# I2C-OneWire_Probes.net
KiCad netlist of a schematic drawn in EAGLE
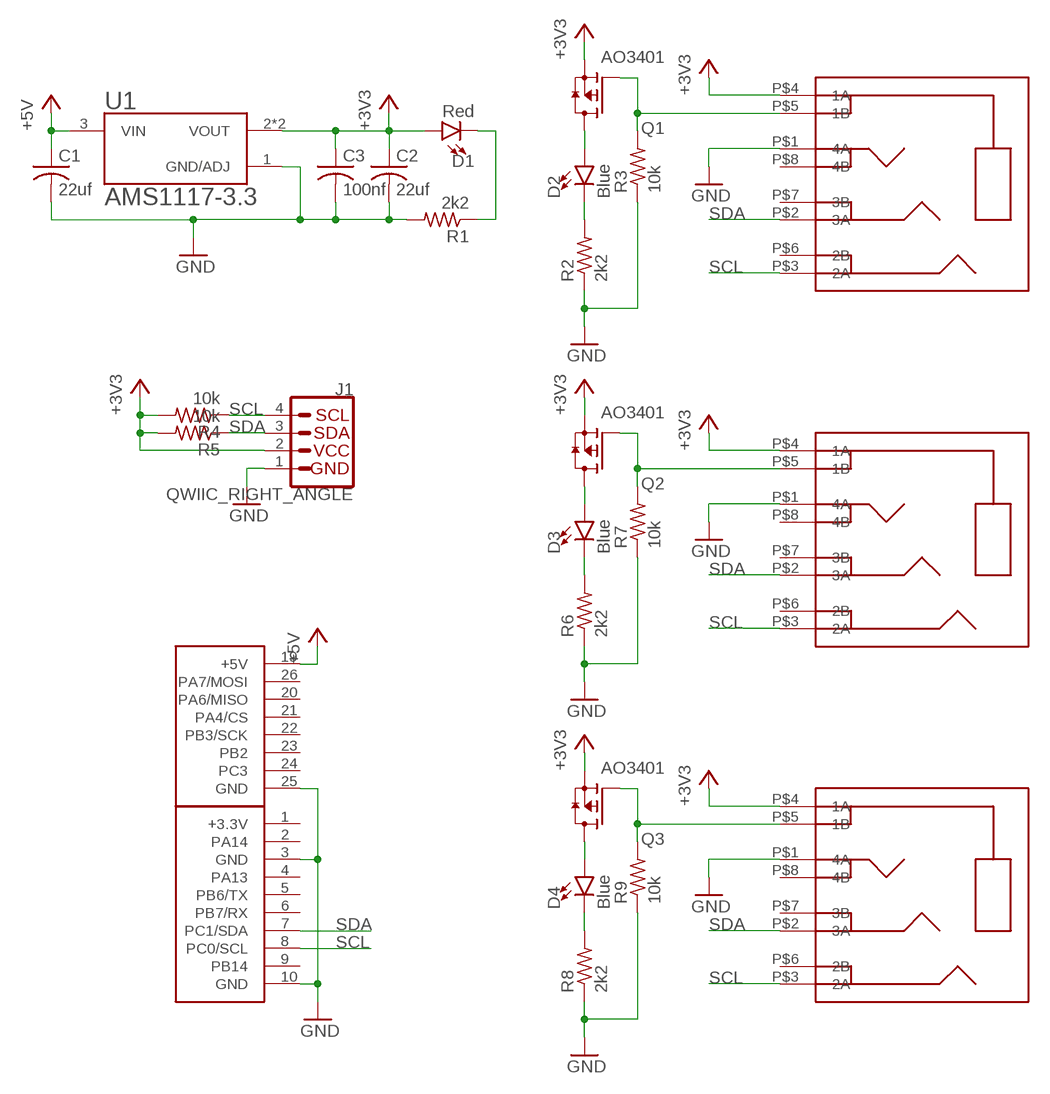
[diagram p0: schematic, sheet 1]

(export (version "E")
  (design (tool "Eeschema 10.0.6"))
  (components
    (comp (ref "C1")
      (value "22uf")
      (footprint "eagle-import:C3216")
      (libsource (lib "eagle-import") (part "C-USC3216"))
    )
    (comp (ref "C2")
      (value "22uf")
      (footprint "eagle-import:C3216")
      (libsource (lib "eagle-import") (part "C-USC3216"))
    )
    (comp (ref "C3")
      (value "100nf")
      (footprint "eagle-import:C0805")
      (libsource (lib "eagle-import") (part "C-USC0805"))
    )
    (comp (ref "D1")
      (value "Red")
      (footprint "eagle-import:LED-1206")
      (libsource (lib "eagle-import") (part "LED-RED1206"))
    )
    (comp (ref "D2")
      (value "Blue")
      (footprint "eagle-import:LED-1206")
      (libsource (lib "eagle-import") (part "LED-BLUE1206"))
    )
    (comp (ref "D3")
      (value "Blue")
      (footprint "eagle-import:LED-1206")
      (libsource (lib "eagle-import") (part "LED-BLUE1206"))
    )
    (comp (ref "D4")
      (value "Blue")
      (footprint "eagle-import:LED-1206")
      (libsource (lib "eagle-import") (part "LED-BLUE1206"))
    )
    (comp (ref "J1")
      (value "QWIIC_RIGHT_ANGLE")
      (footprint "eagle-import:JST04_1MM_RA")
      (libsource (lib "eagle-import") (part "QWIIC_CONNECTORJS-1MM"))
    )
    (comp (ref "Q1")
      (value "AO3401")
      (footprint "eagle-import:AO3401")
      (fields (field (name "MANUFACTURER") "Diodes Inc."))
      (libsource (lib "eagle-import") (part "AO3401"))
    )
    (comp (ref "Q2")
      (value "AO3401")
      (footprint "eagle-import:AO3401")
      (fields (field (name "MANUFACTURER") "Diodes Inc."))
      (libsource (lib "eagle-import") (part "AO3401"))
    )
    (comp (ref "Q3")
      (value "AO3401")
      (footprint "eagle-import:AO3401")
      (fields (field (name "MANUFACTURER") "Diodes Inc."))
      (libsource (lib "eagle-import") (part "AO3401"))
    )
    (comp (ref "R1")
      (value "2k2")
      (footprint "eagle-import:R0805")
      (libsource (lib "eagle-import") (part "R-US_R0805"))
    )
    (comp (ref "R2")
      (value "2k2")
      (footprint "eagle-import:R0805")
      (libsource (lib "eagle-import") (part "R-US_R0805"))
    )
    (comp (ref "R3")
      (value "10k")
      (footprint "eagle-import:R0805")
      (libsource (lib "eagle-import") (part "R-US_R0805"))
    )
    (comp (ref "R4")
      (value "10k")
      (footprint "eagle-import:R0805")
      (libsource (lib "eagle-import") (part "R-US_R0805"))
    )
    (comp (ref "R5")
      (value "10k")
      (footprint "eagle-import:R0805")
      (libsource (lib "eagle-import") (part "R-US_R0805"))
    )
    (comp (ref "R6")
      (value "2k2")
      (footprint "eagle-import:R0805")
      (libsource (lib "eagle-import") (part "R-US_R0805"))
    )
    (comp (ref "R7")
      (value "10k")
      (footprint "eagle-import:R0805")
      (libsource (lib "eagle-import") (part "R-US_R0805"))
    )
    (comp (ref "R8")
      (value "2k2")
      (footprint "eagle-import:R0805")
      (libsource (lib "eagle-import") (part "R-US_R0805"))
    )
    (comp (ref "R9")
      (value "10k")
      (footprint "eagle-import:R0805")
      (libsource (lib "eagle-import") (part "R-US_R0805"))
    )
    (comp (ref "U$1")
      (value "BOTH-SMD")
      (footprint "eagle-import:BOTH-SMD")
      (libsource (lib "eagle-import") (part "BOTH-SMD"))
    )
    (comp (ref "U$2")
      (value "PJ-3938PJ")
      (footprint "eagle-import:PJ-3938PJ")
      (libsource (lib "eagle-import") (part "PJ-3938PJ"))
    )
    (comp (ref "U$3")
      (value "PJ-3938PJ")
      (footprint "eagle-import:PJ-3938PJ")
      (libsource (lib "eagle-import") (part "PJ-3938PJ"))
    )
    (comp (ref "U$4")
      (value "PJ-3938PJ")
      (footprint "eagle-import:PJ-3938PJ")
      (libsource (lib "eagle-import") (part "PJ-3938PJ"))
    )
    (comp (ref "U1")
      (value "AMS1117-3.3")
      (footprint "eagle-import:SOT229P700X180-4N")
      (fields (field (name "MF") "Advanced Monolithic Systems"))
      (libsource (lib "eagle-import") (part "AMS1117-3.3"))
    )
  )
  (nets
    (net (code "1") (name "+3V3") (class "Default")
      (node (ref "C2") (pin "1") (pinfunction "1_1") (pintype "passive"))
      (node (ref "C3") (pin "1") (pinfunction "1_1") (pintype "passive"))
      (node (ref "D1") (pin "A") (pinfunction "A_A") (pintype "passive"))
      (node (ref "J1") (pin "2") (pinfunction "2_2") (pintype "power_in"))
      (node (ref "Q1") (pin "2") (pinfunction "S_2") (pintype "passive"))
      (node (ref "Q2") (pin "2") (pinfunction "S_2") (pintype "passive"))
      (node (ref "Q3") (pin "2") (pinfunction "S_2") (pintype "passive"))
      (node (ref "R4") (pin "2") (pinfunction "2_2") (pintype "passive"))
      (node (ref "R5") (pin "2") (pinfunction "2_2") (pintype "passive"))
      (node (ref "U$2") (pin "P$4") (pinfunction "1A_P$4") (pintype "bidirectional"))
      (node (ref "U$3") (pin "P$4") (pinfunction "1A_P$4") (pintype "bidirectional"))
      (node (ref "U$4") (pin "P$4") (pinfunction "1A_P$4") (pintype "bidirectional"))
      (node (ref "U1") (pin "2") (pinfunction "VOUT_2") (pintype "output"))
      (node (ref "U1") (pin "4") (pinfunction "VOUT_4") (pintype "output"))
    )
    (net (code "2") (name "+5V") (class "Default")
      (node (ref "C1") (pin "1") (pinfunction "1_1") (pintype "passive"))
      (node (ref "U$1") (pin "19") (pinfunction "+5V_19") (pintype "bidirectional"))
      (node (ref "U1") (pin "3") (pinfunction "VIN_3") (pintype "input"))
    )
    (net (code "3") (name "/SCL") (class "Default")
      (node (ref "J1") (pin "4") (pinfunction "4_4") (pintype "passive"))
      (node (ref "R4") (pin "1") (pinfunction "1_1") (pintype "passive"))
      (node (ref "U$1") (pin "8") (pinfunction "PC0/SCL_8") (pintype "bidirectional"))
      (node (ref "U$2") (pin "P$3") (pinfunction "2A_P$3") (pintype "bidirectional"))
      (node (ref "U$3") (pin "P$3") (pinfunction "2A_P$3") (pintype "bidirectional"))
      (node (ref "U$4") (pin "P$3") (pinfunction "2A_P$3") (pintype "bidirectional"))
    )
    (net (code "4") (name "/SDA") (class "Default")
      (node (ref "J1") (pin "3") (pinfunction "3_3") (pintype "passive"))
      (node (ref "R5") (pin "1") (pinfunction "1_1") (pintype "passive"))
      (node (ref "U$1") (pin "7") (pinfunction "PC1/SDA_7") (pintype "bidirectional"))
      (node (ref "U$2") (pin "P$2") (pinfunction "3A_P$2") (pintype "bidirectional"))
      (node (ref "U$3") (pin "P$2") (pinfunction "3A_P$2") (pintype "bidirectional"))
      (node (ref "U$4") (pin "P$2") (pinfunction "3A_P$2") (pintype "bidirectional"))
    )
    (net (code "5") (name "GND") (class "Default")
      (node (ref "C1") (pin "2") (pinfunction "2_2") (pintype "passive"))
      (node (ref "C2") (pin "2") (pinfunction "2_2") (pintype "passive"))
      (node (ref "C3") (pin "2") (pinfunction "2_2") (pintype "passive"))
      (node (ref "J1") (pin "1") (pinfunction "1_1") (pintype "power_in"))
      (node (ref "R1") (pin "2") (pinfunction "2_2") (pintype "passive"))
      (node (ref "R2") (pin "1") (pinfunction "1_1") (pintype "passive"))
      (node (ref "R3") (pin "1") (pinfunction "1_1") (pintype "passive"))
      (node (ref "R6") (pin "1") (pinfunction "1_1") (pintype "passive"))
      (node (ref "R7") (pin "1") (pinfunction "1_1") (pintype "passive"))
      (node (ref "R8") (pin "1") (pinfunction "1_1") (pintype "passive"))
      (node (ref "R9") (pin "1") (pinfunction "1_1") (pintype "passive"))
      (node (ref "U$1") (pin "10") (pinfunction "GND_10") (pintype "bidirectional"))
      (node (ref "U$1") (pin "25") (pinfunction "GND_25") (pintype "bidirectional"))
      (node (ref "U$1") (pin "3") (pinfunction "GND_3") (pintype "bidirectional"))
      (node (ref "U$2") (pin "P$1") (pinfunction "4A_P$1") (pintype "bidirectional"))
      (node (ref "U$3") (pin "P$1") (pinfunction "4A_P$1") (pintype "bidirectional"))
      (node (ref "U$4") (pin "P$1") (pinfunction "4A_P$1") (pintype "bidirectional"))
      (node (ref "U1") (pin "1") (pinfunction "GND/ADJ_1") (pintype "power_in"))
    )
    (net (code "6") (name "Net-(D1-PadC)") (class "Default")
      (node (ref "D1") (pin "C") (pinfunction "C_C") (pintype "passive"))
      (node (ref "R1") (pin "1") (pinfunction "1_1") (pintype "passive"))
    )
    (net (code "7") (name "Net-(D2-PadC)") (class "Default")
      (node (ref "D2") (pin "C") (pinfunction "C_C") (pintype "passive"))
      (node (ref "R2") (pin "2") (pinfunction "2_2") (pintype "passive"))
    )
    (net (code "8") (name "Net-(D3-PadC)") (class "Default")
      (node (ref "D3") (pin "C") (pinfunction "C_C") (pintype "passive"))
      (node (ref "R6") (pin "2") (pinfunction "2_2") (pintype "passive"))
    )
    (net (code "9") (name "Net-(D4-PadC)") (class "Default")
      (node (ref "D4") (pin "C") (pinfunction "C_C") (pintype "passive"))
      (node (ref "R8") (pin "2") (pinfunction "2_2") (pintype "passive"))
    )
    (net (code "10") (name "Net-(Q1-D)") (class "Default")
      (node (ref "D2") (pin "A") (pinfunction "A_A") (pintype "passive"))
      (node (ref "Q1") (pin "3") (pinfunction "D_3") (pintype "passive"))
    )
    (net (code "11") (name "Net-(Q1-G)") (class "Default")
      (node (ref "Q1") (pin "1") (pinfunction "G_1") (pintype "passive"))
      (node (ref "R3") (pin "2") (pinfunction "2_2") (pintype "passive"))
      (node (ref "U$2") (pin "P$5") (pinfunction "1B_P$5") (pintype "bidirectional"))
    )
    (net (code "12") (name "Net-(Q2-D)") (class "Default")
      (node (ref "D3") (pin "A") (pinfunction "A_A") (pintype "passive"))
      (node (ref "Q2") (pin "3") (pinfunction "D_3") (pintype "passive"))
    )
    (net (code "13") (name "Net-(Q2-G)") (class "Default")
      (node (ref "Q2") (pin "1") (pinfunction "G_1") (pintype "passive"))
      (node (ref "R7") (pin "2") (pinfunction "2_2") (pintype "passive"))
      (node (ref "U$3") (pin "P$5") (pinfunction "1B_P$5") (pintype "bidirectional"))
    )
    (net (code "14") (name "Net-(Q3-D)") (class "Default")
      (node (ref "D4") (pin "A") (pinfunction "A_A") (pintype "passive"))
      (node (ref "Q3") (pin "3") (pinfunction "D_3") (pintype "passive"))
    )
    (net (code "15") (name "Net-(Q3-G)") (class "Default")
      (node (ref "Q3") (pin "1") (pinfunction "G_1") (pintype "passive"))
      (node (ref "R9") (pin "2") (pinfunction "2_2") (pintype "passive"))
      (node (ref "U$4") (pin "P$5") (pinfunction "1B_P$5") (pintype "bidirectional"))
    )
    (net (code "16") (name "unconnected-(U$1A-PA4{slash}CS-Pad21)") (class "Default")
      (node (ref "U$1") (pin "21") (pinfunction "PA4/CS_21") (pintype "bidirectional"))
    )
    (net (code "17") (name "unconnected-(U$1A-PA6{slash}MISO-Pad20)") (class "Default")
      (node (ref "U$1") (pin "20") (pinfunction "PA6/MISO_20") (pintype "bidirectional"))
    )
    (net (code "18") (name "unconnected-(U$1A-PA7{slash}MOSI-Pad26)") (class "Default")
      (node (ref "U$1") (pin "26") (pinfunction "PA7/MOSI_26") (pintype "bidirectional"))
    )
    (net (code "19") (name "unconnected-(U$1A-PB2-Pad23)") (class "Default")
      (node (ref "U$1") (pin "23") (pinfunction "PB2_23") (pintype "bidirectional"))
    )
    (net (code "20") (name "unconnected-(U$1A-PB3{slash}SCK-Pad22)") (class "Default")
      (node (ref "U$1") (pin "22") (pinfunction "PB3/SCK_22") (pintype "bidirectional"))
    )
    (net (code "21") (name "unconnected-(U$1A-PC3-Pad24)") (class "Default")
      (node (ref "U$1") (pin "24") (pinfunction "PC3_24") (pintype "bidirectional"))
    )
    (net (code "22") (name "unconnected-(U$1B-+3.3V-Pad1)") (class "Default")
      (node (ref "U$1") (pin "1") (pinfunction "+3.3V_1") (pintype "bidirectional"))
    )
    (net (code "23") (name "unconnected-(U$1B-PA13-Pad4)") (class "Default")
      (node (ref "U$1") (pin "4") (pinfunction "PA13_4") (pintype "bidirectional"))
    )
    (net (code "24") (name "unconnected-(U$1B-PA14-Pad2)") (class "Default")
      (node (ref "U$1") (pin "2") (pinfunction "PA14_2") (pintype "bidirectional"))
    )
    (net (code "25") (name "unconnected-(U$1B-PB6{slash}TX-Pad5)") (class "Default")
      (node (ref "U$1") (pin "5") (pinfunction "PB6/TX_5") (pintype "bidirectional"))
    )
    (net (code "26") (name "unconnected-(U$1B-PB7{slash}RX-Pad6)") (class "Default")
      (node (ref "U$1") (pin "6") (pinfunction "PB7/RX_6") (pintype "bidirectional"))
    )
    (net (code "27") (name "unconnected-(U$1B-PB14-Pad9)") (class "Default")
      (node (ref "U$1") (pin "9") (pinfunction "PB14_9") (pintype "bidirectional"))
    )
    (net (code "28") (name "unconnected-(U$2-2B-PadP$6)") (class "Default")
      (node (ref "U$2") (pin "P$6") (pinfunction "2B_P$6") (pintype "bidirectional"))
    )
    (net (code "29") (name "unconnected-(U$2-3B-PadP$7)") (class "Default")
      (node (ref "U$2") (pin "P$7") (pinfunction "3B_P$7") (pintype "bidirectional"))
    )
    (net (code "30") (name "unconnected-(U$2-4B-PadP$8)") (class "Default")
      (node (ref "U$2") (pin "P$8") (pinfunction "4B_P$8") (pintype "bidirectional"))
    )
    (net (code "31") (name "unconnected-(U$3-2B-PadP$6)") (class "Default")
      (node (ref "U$3") (pin "P$6") (pinfunction "2B_P$6") (pintype "bidirectional"))
    )
    (net (code "32") (name "unconnected-(U$3-3B-PadP$7)") (class "Default")
      (node (ref "U$3") (pin "P$7") (pinfunction "3B_P$7") (pintype "bidirectional"))
    )
    (net (code "33") (name "unconnected-(U$3-4B-PadP$8)") (class "Default")
      (node (ref "U$3") (pin "P$8") (pinfunction "4B_P$8") (pintype "bidirectional"))
    )
    (net (code "34") (name "unconnected-(U$4-2B-PadP$6)") (class "Default")
      (node (ref "U$4") (pin "P$6") (pinfunction "2B_P$6") (pintype "bidirectional"))
    )
    (net (code "35") (name "unconnected-(U$4-3B-PadP$7)") (class "Default")
      (node (ref "U$4") (pin "P$7") (pinfunction "3B_P$7") (pintype "bidirectional"))
    )
    (net (code "36") (name "unconnected-(U$4-4B-PadP$8)") (class "Default")
      (node (ref "U$4") (pin "P$8") (pinfunction "4B_P$8") (pintype "bidirectional"))
    )
  )
)
